# cpu.net
KiCad netlist of a schematic drawn in Altium Designer
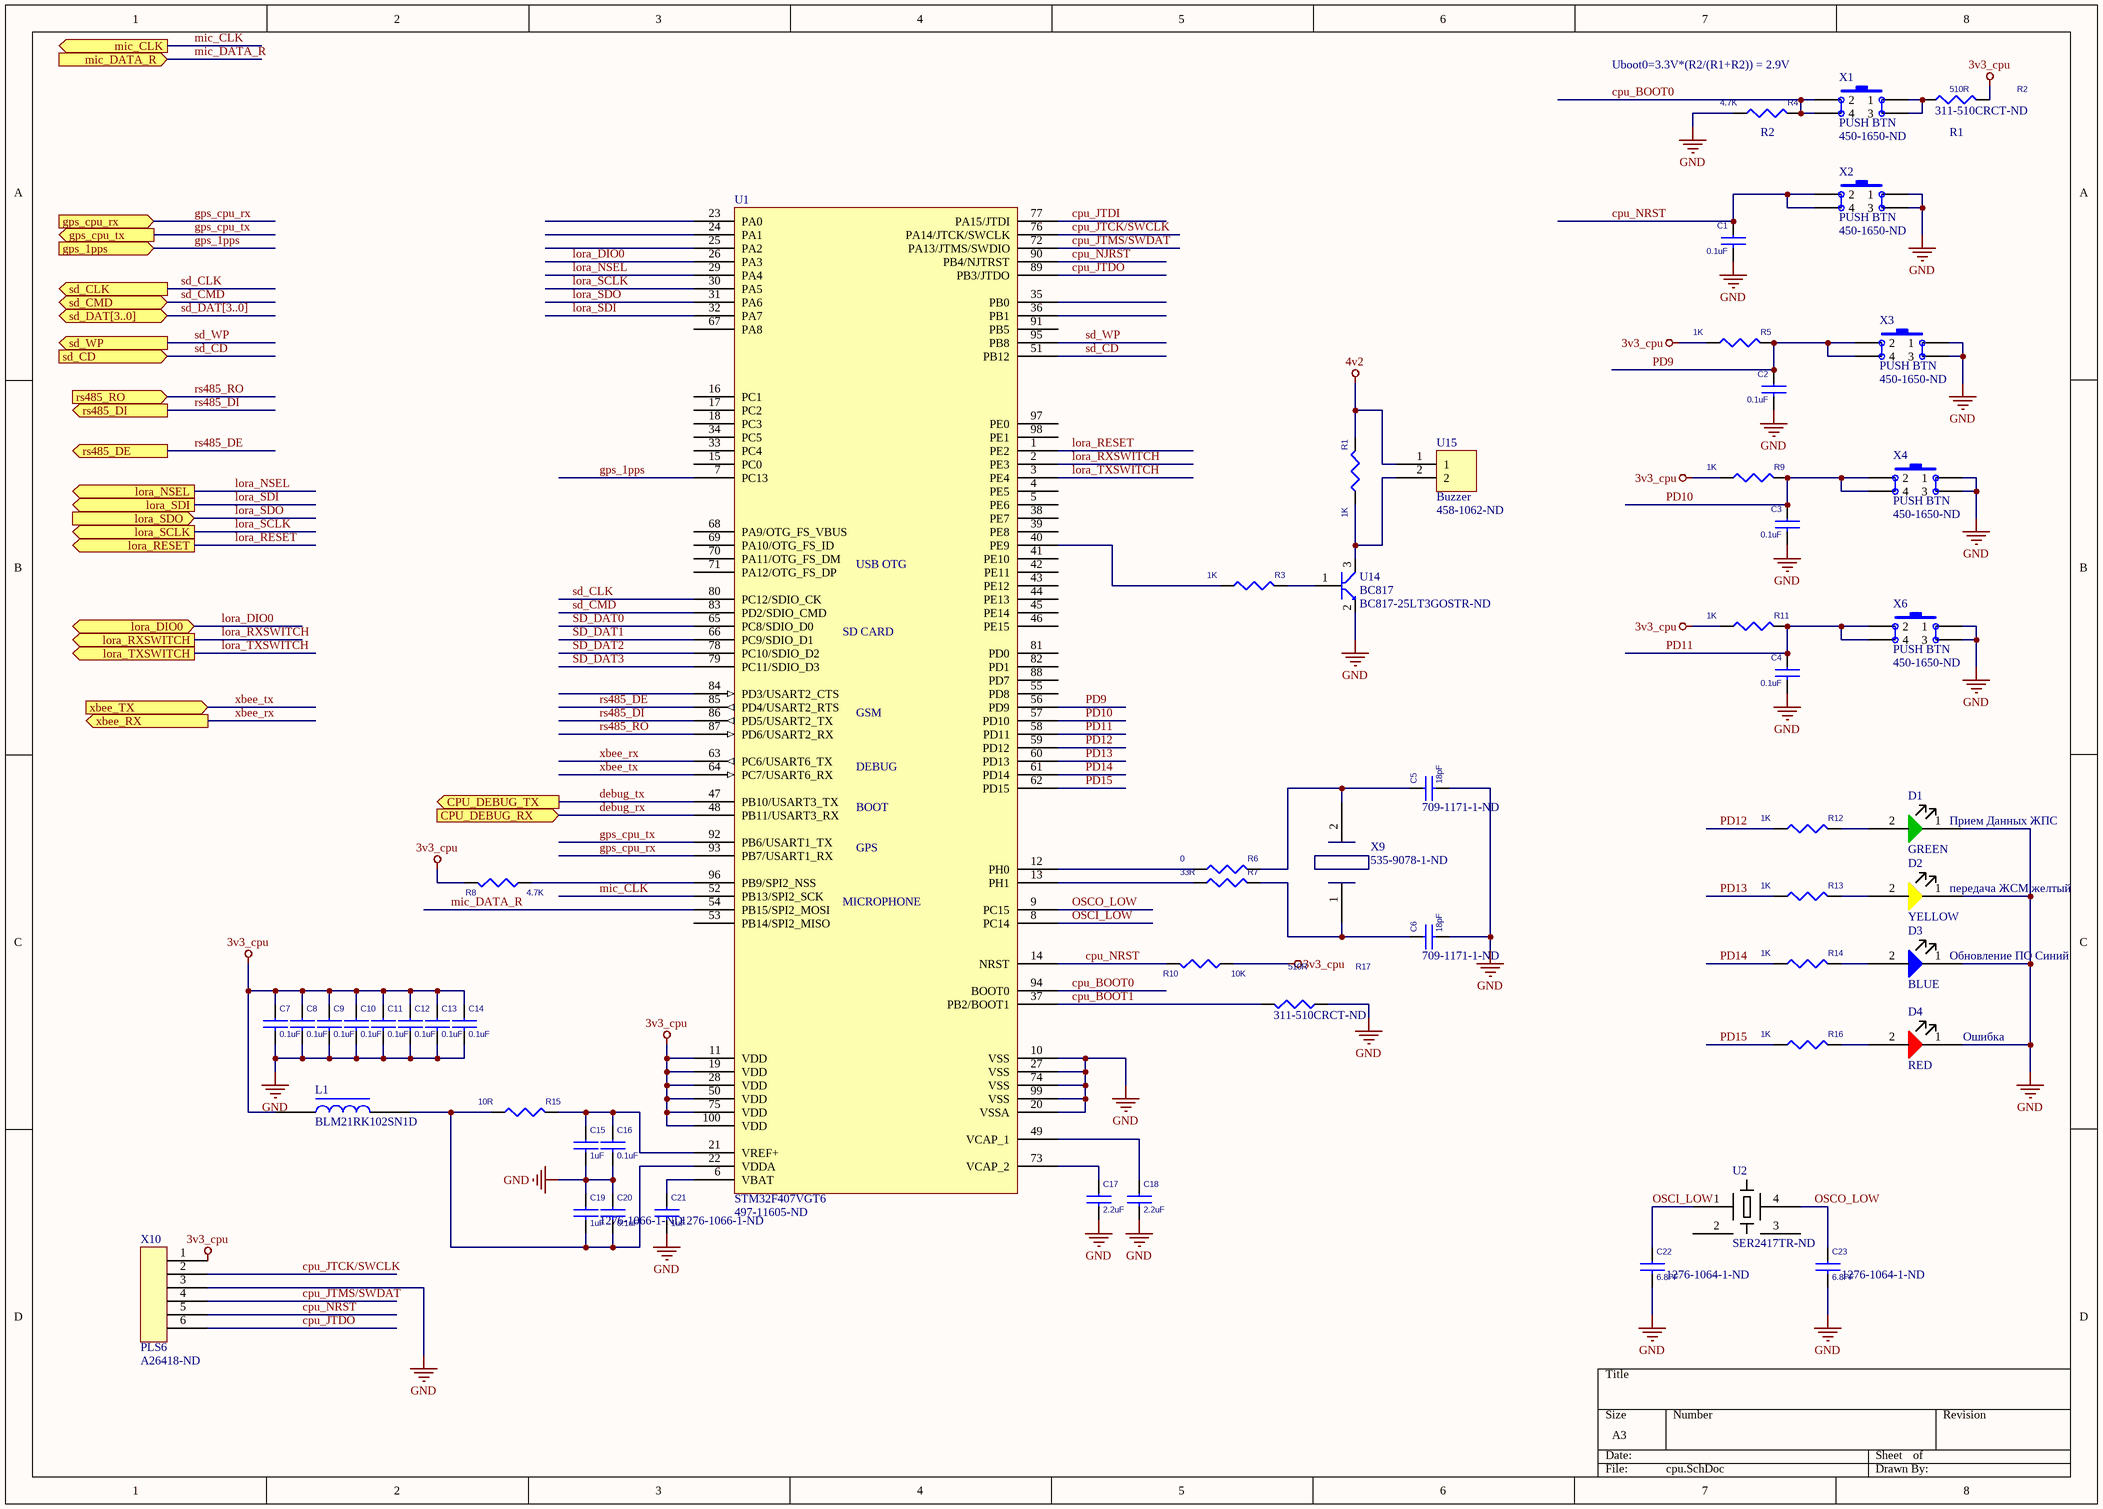
[diagram p0: cpu.SchDoc]

(export (version "E")
  (design (tool "Eeschema 10.0.6"))
  (components
    (comp (ref "C1")
      (value "0.1uF")
      (footprint "CAPC2012X09M")
      (description "CAP CER 0.1UF 25V 10% X7R 0805")
      (libsource (lib "Capacitors") (part "CAP_SMD_0.1UF_10%"))
    )
    (comp (ref "C2")
      (value "0.1uF")
      (footprint "CAPC2012X09M")
      (description "CAP CER 0.1UF 25V 10% X7R 0805")
      (libsource (lib "Capacitors") (part "CAP_SMD_0.1UF_10%"))
    )
    (comp (ref "C3")
      (value "0.1uF")
      (footprint "CAPC2012X09M")
      (description "CAP CER 0.1UF 25V 10% X7R 0805")
      (libsource (lib "Capacitors") (part "CAP_SMD_0.1UF_10%"))
    )
    (comp (ref "C4")
      (value "0.1uF")
      (footprint "CAPC2012X09M")
      (description "CAP CER 0.1UF 25V 10% X7R 0805")
      (libsource (lib "Capacitors") (part "CAP_SMD_0.1UF_10%"))
    )
    (comp (ref "C5")
      (value "18pF")
      (footprint "CAPC2012X09M")
      (description "CAP CER 27PF 200V 5% NP0 0805")
      (fields (field (name "SUPPLIER PART NUMBER 1") "709-1171-1-ND"))
      (libsource (lib "Capacitors") (part "CAP_SMD_18PF_5%"))
    )
    (comp (ref "C6")
      (value "18pF")
      (footprint "CAPC2012X09M")
      (description "CAP CER 27PF 200V 5% NP0 0805")
      (fields (field (name "SUPPLIER PART NUMBER 1") "709-1171-1-ND"))
      (libsource (lib "Capacitors") (part "CAP_SMD_18PF_5%"))
    )
    (comp (ref "C7")
      (value "0.1uF")
      (footprint "CAPC2012X09M")
      (description "CAP CER 0.1UF 25V 10% X7R 0805")
      (libsource (lib "Capacitors") (part "CAP_SMD_0.1UF_10%"))
    )
    (comp (ref "C8")
      (value "0.1uF")
      (footprint "CAPC2012X09M")
      (description "CAP CER 0.1UF 25V 10% X7R 0805")
      (libsource (lib "Capacitors") (part "CAP_SMD_0.1UF_10%"))
    )
    (comp (ref "C9")
      (value "0.1uF")
      (footprint "CAPC2012X09M")
      (description "CAP CER 0.1UF 25V 10% X7R 0805")
      (libsource (lib "Capacitors") (part "CAP_SMD_0.1UF_10%"))
    )
    (comp (ref "C10")
      (value "0.1uF")
      (footprint "CAPC2012X09M")
      (description "CAP CER 0.1UF 25V 10% X7R 0805")
      (libsource (lib "Capacitors") (part "CAP_SMD_0.1UF_10%"))
    )
    (comp (ref "C11")
      (value "0.1uF")
      (footprint "CAPC2012X09M")
      (description "CAP CER 0.1UF 25V 10% X7R 0805")
      (libsource (lib "Capacitors") (part "CAP_SMD_0.1UF_10%"))
    )
    (comp (ref "C12")
      (value "0.1uF")
      (footprint "CAPC2012X09M")
      (description "CAP CER 0.1UF 25V 10% X7R 0805")
      (libsource (lib "Capacitors") (part "CAP_SMD_0.1UF_10%"))
    )
    (comp (ref "C13")
      (value "0.1uF")
      (footprint "CAPC2012X09M")
      (description "CAP CER 0.1UF 25V 10% X7R 0805")
      (libsource (lib "Capacitors") (part "CAP_SMD_0.1UF_10%"))
    )
    (comp (ref "C14")
      (value "0.1uF")
      (footprint "CAPC2012X09M")
      (description "CAP CER 0.1UF 25V 10% X7R 0805")
      (libsource (lib "Capacitors") (part "CAP_SMD_0.1UF_10%"))
    )
    (comp (ref "C15")
      (value "1uF")
      (footprint "CAPC2012X09M")
      (description "MLCC; 1uF; 25V; X7R; ±10%; SMD; 0805;")
      (libsource (lib "Capacitors") (part "CAP_SMD_1uF_10%"))
    )
    (comp (ref "C16")
      (value "0.1uF")
      (footprint "CAPC2012X09M")
      (description "CAP CER 0.1UF 25V 10% X7R 0805")
      (libsource (lib "Capacitors") (part "CAP_SMD_0.1UF_10%"))
    )
    (comp (ref "C17")
      (value "2.2uF")
      (footprint "CAPC2012X09M")
      (description "CAP CER 2.2UF 16V 10% X5R 0805")
      (libsource (lib "Capacitors") (part "CAP_SMD_2.2uF_10%"))
    )
    (comp (ref "C18")
      (value "2.2uF")
      (footprint "CAPC2012X09M")
      (description "CAP CER 2.2UF 16V 10% X5R 0805")
      (libsource (lib "Capacitors") (part "CAP_SMD_2.2uF_10%"))
    )
    (comp (ref "C19")
      (value "1uF")
      (footprint "CAPC2012X09M")
      (description "MLCC; 1uF; 25V; X7R; ±10%; SMD; 0805;")
      (fields (field (name "SUPPLIER PART NUMBER 1") "1276-1066-1-ND"))
      (libsource (lib "Capacitors") (part "CAP_SMD_1uF_10%"))
    )
    (comp (ref "C20")
      (value "0.1uF")
      (footprint "CAPC2012X09M")
      (description "CAP CER 0.1UF 25V 10% X7R 0805")
      (libsource (lib "Capacitors") (part "CAP_SMD_0.1UF_10%"))
    )
    (comp (ref "C21")
      (value "1uF")
      (footprint "CAPC2012X09M")
      (description "MLCC; 1uF; 25V; X7R; ±10%; SMD; 0805;")
      (fields (field (name "SUPPLIER PART NUMBER 1") "1276-1066-1-ND"))
      (libsource (lib "Capacitors") (part "CAP_SMD_1uF_10%"))
    )
    (comp (ref "C22")
      (value "6.8PF")
      (footprint "CAPC2012X09M")
      (description "CAP MLCC 6.8PF 50V 5% NP0 0805")
      (fields (field (name "SUPPLIER PART NUMBER 1") "1276-1064-1-ND"))
      (libsource (lib "Capacitors") (part "CAP_SMD_6.8PF_5%"))
    )
    (comp (ref "C23")
      (value "6.8PF")
      (footprint "CAPC2012X09M")
      (description "CAP MLCC 6.8PF 50V 5% NP0 0805")
      (fields (field (name "SUPPLIER PART NUMBER 1") "1276-1064-1-ND"))
      (libsource (lib "Capacitors") (part "CAP_SMD_6.8PF_5%"))
    )
    (comp (ref "D1")
      (value "GREEN")
      (footprint "DIOC2012X11N")
      (libsource (lib "Passive") (part "LED_GREEN"))
    )
    (comp (ref "D2")
      (value "YELLOW")
      (footprint "DIOC2012X11N")
      (libsource (lib "Passive") (part "LED_YELLOW"))
    )
    (comp (ref "D3") (value "BLUE") (footprint "DIOC2012X11N") (libsource (lib "Passive") (part "LED_BLUE")))
    (comp (ref "D4") (value "RED") (footprint "DIOC2012X11N") (libsource (lib "Passive") (part "LED_RED")))
    (comp (ref "L1")
      (value "BLM21RK102SN1D")
      (footprint "DIOC2012X11N")
      (libsource (lib "Passive") (part "BLM21RK102SN1D"))
    )
    (comp (ref "R1")
      (value "1K")
      (footprint "RESC2013X06M")
      (description "RES - 1K OHM, 5%, 1/8W, 0805 SMD")
      (libsource (lib "Resistors") (part "RES_SMD_1K_5%"))
    )
    (comp (ref "R2")
      (value "510R")
      (footprint "RESC2013X06M")
      (description "RES - 510 OHM, 5%, 1/8W, 0805 SMD")
      (fields (field (name "SUPPLIER PART NUMBER 1") "311-510CRCT-ND"))
      (libsource (lib "Resistors") (part "RES_SMD_510_5%"))
    )
    (comp (ref "R3")
      (value "1K")
      (footprint "RESC2013X06M")
      (description "RES - 1K OHM, 5%, 1/8W, 0805 SMD")
      (libsource (lib "Resistors") (part "RES_SMD_1K_5%"))
    )
    (comp (ref "R4")
      (value "4.7K")
      (footprint "RESC2013X06M")
      (description "RES 4.7K OHM 1/8W 1% 0805 SMD")
      (libsource (lib "Resistors") (part "RES_SMD_4.7K_1%"))
    )
    (comp (ref "R5")
      (value "1K")
      (footprint "RESC2013X06M")
      (description "RES - 1K OHM, 5%, 1/8W, 0805 SMD")
      (libsource (lib "Resistors") (part "RES_SMD_1K_5%"))
    )
    (comp (ref "R6")
      (value "0")
      (footprint "RESC2013X06M")
      (description "RES 0.0 OHM 1/8W JUMP 0805 SMD")
      (libsource (lib "Resistors") (part "RES_SMD_0"))
    )
    (comp (ref "R7")
      (value "33R")
      (footprint "RESC2013X06M")
      (description "RES - 33 OHM, 5%, 1/8W, 0805 SMD")
      (libsource (lib "Resistors") (part "RES_SMD_33R_5%"))
    )
    (comp (ref "R8")
      (value "4.7K")
      (footprint "RESC2013X06M")
      (description "RES 4.7K OHM 1/8W 1% 0805 SMD")
      (libsource (lib "Resistors") (part "RES_SMD_4.7K_1%"))
    )
    (comp (ref "R9")
      (value "1K")
      (footprint "RESC2013X06M")
      (description "RES - 1K OHM, 5%, 1/8W, 0805 SMD")
      (libsource (lib "Resistors") (part "RES_SMD_1K_5%"))
    )
    (comp (ref "R10")
      (value "10K")
      (footprint "RESC2013X06M")
      (description "RES 10K OHM 1/8W 5% 0805 SMD")
      (libsource (lib "Resistors") (part "RES_SMD_10K_5%"))
    )
    (comp (ref "R11")
      (value "1K")
      (footprint "RESC2013X06M")
      (description "RES - 1K OHM, 5%, 1/8W, 0805 SMD")
      (libsource (lib "Resistors") (part "RES_SMD_1K_5%"))
    )
    (comp (ref "R12")
      (value "1K")
      (footprint "RESC2013X06M")
      (description "RES - 1K OHM, 5%, 1/8W, 0805 SMD")
      (libsource (lib "Resistors") (part "RES_SMD_1K_5%"))
    )
    (comp (ref "R13")
      (value "1K")
      (footprint "RESC2013X06M")
      (description "RES - 1K OHM, 5%, 1/8W, 0805 SMD")
      (libsource (lib "Resistors") (part "RES_SMD_1K_5%"))
    )
    (comp (ref "R14")
      (value "1K")
      (footprint "RESC2013X06M")
      (description "RES - 1K OHM, 5%, 1/8W, 0805 SMD")
      (libsource (lib "Resistors") (part "RES_SMD_1K_5%"))
    )
    (comp (ref "R15")
      (value "10R")
      (footprint "RESC2013X06M")
      (description "RES 10 OHM 1/8W 1% 0805 SMD")
      (libsource (lib "Resistors") (part "RES_SMD_10R_5%"))
    )
    (comp (ref "R16")
      (value "1K")
      (footprint "RESC2013X06M")
      (description "RES - 1K OHM, 5%, 1/8W, 0805 SMD")
      (libsource (lib "Resistors") (part "RES_SMD_1K_5%"))
    )
    (comp (ref "R17")
      (value "510R")
      (footprint "RESC2013X06M")
      (description "RES - 510 OHM, 5%, 1/8W, 0805 SMD")
      (fields (field (name "SUPPLIER PART NUMBER 1") "311-510CRCT-ND"))
      (libsource (lib "Resistors") (part "RES_SMD_510_5%"))
    )
    (comp (ref "U1")
      (value "STM32F407VGT6")
      (footprint "TSQFP50P1600X1600X160-100M")
      (fields (field (name "SUPPLIER PART NUMBER 1") "497-11605-ND"))
      (libsource (lib "TruthEar") (part "STM32F407VGT6"))
    )
    (comp (ref "U2")
      (value "32.768KHZ")
      (footprint "SOJ550P380X254-4M")
      (fields (field (name "SUPPLIER PART NUMBER 1") "SER2417TR-ND"))
      (libsource (lib "TruthEar") (part "MC-306"))
    )
    (comp (ref "U14")
      (value "BC817")
      (footprint "SOT95P237X111-3N_SOT-23")
      (fields (field (name "SUPPLIER PART NUMBER 1") "BC817-25LT3GOSTR-ND"))
      (libsource (lib "TruthEar") (part "BC817"))
    )
    (comp (ref "U15")
      (value "Buzzer")
      (footprint "pb1224pe")
      (fields (field (name "SUPPLIER PART NUMBER 1") "458-1062-ND"))
      (libsource (lib "TruthEar") (part "pb-1224pe-05q"))
    )
    (comp (ref "X1")
      (value "PUSH BTN")
      (footprint "PUSHBTN")
      (fields (field (name "SUPPLIER PART NUMBER 1") "450-1650-ND"))
      (libsource (lib "TruthEar") (part "SW1"))
    )
    (comp (ref "X2")
      (value "PUSH BTN")
      (footprint "PUSHBTN")
      (fields (field (name "SUPPLIER PART NUMBER 1") "450-1650-ND"))
      (libsource (lib "TruthEar") (part "SW1"))
    )
    (comp (ref "X3")
      (value "PUSH BTN")
      (footprint "PUSHBTN")
      (fields (field (name "SUPPLIER PART NUMBER 1") "450-1650-ND"))
      (libsource (lib "TruthEar") (part "SW1"))
    )
    (comp (ref "X4")
      (value "PUSH BTN")
      (footprint "PUSHBTN")
      (fields (field (name "SUPPLIER PART NUMBER 1") "450-1650-ND"))
      (libsource (lib "TruthEar") (part "SW1"))
    )
    (comp (ref "X6")
      (value "PUSH BTN")
      (footprint "PUSHBTN")
      (fields (field (name "SUPPLIER PART NUMBER 1") "450-1650-ND"))
      (libsource (lib "TruthEar") (part "SW1"))
    )
    (comp (ref "X9")
      (value "25.000Mhz")
      (footprint "SODFL1270X420-2L")
      (fields (field (name "SUPPLIER PART NUMBER 1") "535-9078-1-ND"))
      (libsource (lib "TruthEar") (part "OSC25M"))
    )
    (comp (ref "X10")
      (value "PLS6")
      (footprint "PLS6")
      (fields (field (name "SUPPLIER PART NUMBER 1") "A26418-ND"))
      (libsource (lib "Connectors") (part "PLS6"))
    )
  )
  (nets
    (net (code "5") (name "/OSCI_LOW") (class "Default")
      (node (ref "C22") (pin "1") (pinfunction "1_1") (pintype "passive"))
      (node (ref "U1") (pin "8") (pinfunction "PC14_8") (pintype "passive"))
      (node (ref "U2") (pin "1") (pinfunction "OSC1_1") (pintype "power_in"))
    )
    (net (code "6") (name "/OSCO_LOW") (class "Default")
      (node (ref "C23") (pin "1") (pinfunction "1_1") (pintype "passive"))
      (node (ref "U1") (pin "9") (pinfunction "PC15_9") (pintype "passive"))
      (node (ref "U2") (pin "4") (pinfunction "OSC2_4") (pintype "power_in"))
    )
    (net (code "7") (name "/PD9") (class "Default")
      (node (ref "C2") (pin "1") (pinfunction "1_1") (pintype "passive"))
      (node (ref "R5") (pin "2") (pinfunction "2_2") (pintype "passive"))
      (node (ref "U1") (pin "56") (pinfunction "PD9_56") (pintype "passive"))
      (node (ref "X3") (pin "2") (pinfunction "2_2") (pintype "passive"))
      (node (ref "X3") (pin "4") (pinfunction "4_4") (pintype "passive"))
    )
    (net (code "8") (name "/PD10") (class "Default")
      (node (ref "C3") (pin "1") (pinfunction "1_1") (pintype "passive"))
      (node (ref "R9") (pin "2") (pinfunction "2_2") (pintype "passive"))
      (node (ref "U1") (pin "57") (pinfunction "PD10_57") (pintype "passive"))
      (node (ref "X4") (pin "2") (pinfunction "2_2") (pintype "passive"))
      (node (ref "X4") (pin "4") (pinfunction "4_4") (pintype "passive"))
    )
    (net (code "9") (name "/PD11") (class "Default")
      (node (ref "C4") (pin "1") (pinfunction "1_1") (pintype "passive"))
      (node (ref "R11") (pin "2") (pinfunction "2_2") (pintype "passive"))
      (node (ref "U1") (pin "58") (pinfunction "PD11_58") (pintype "passive"))
      (node (ref "X6") (pin "2") (pinfunction "2_2") (pintype "passive"))
      (node (ref "X6") (pin "4") (pinfunction "4_4") (pintype "passive"))
    )
    (net (code "10") (name "/PD12") (class "Default")
      (node (ref "R12") (pin "1") (pinfunction "1_1") (pintype "passive"))
      (node (ref "U1") (pin "59") (pinfunction "PD12_59") (pintype "passive"))
    )
    (net (code "11") (name "/PD13") (class "Default")
      (node (ref "R13") (pin "1") (pinfunction "1_1") (pintype "passive"))
      (node (ref "U1") (pin "60") (pinfunction "PD13_60") (pintype "passive"))
    )
    (net (code "12") (name "/PD14") (class "Default")
      (node (ref "R14") (pin "1") (pinfunction "1_1") (pintype "passive"))
      (node (ref "U1") (pin "61") (pinfunction "PD14_61") (pintype "passive"))
    )
    (net (code "13") (name "/PD15") (class "Default")
      (node (ref "R16") (pin "1") (pinfunction "1_1") (pintype "passive"))
      (node (ref "U1") (pin "62") (pinfunction "PD15_62") (pintype "passive"))
    )
    (net (code "14") (name "/SD_DAT0") (class "Default")
      (node (ref "U1") (pin "65") (pinfunction "PC8/SDIO_D0_65") (pintype "passive"))
    )
    (net (code "15") (name "/SD_DAT1") (class "Default")
      (node (ref "U1") (pin "66") (pinfunction "PC9/SDIO_D1_66") (pintype "passive"))
    )
    (net (code "16") (name "/SD_DAT2") (class "Default")
      (node (ref "U1") (pin "78") (pinfunction "PC10/SDIO_D2_78") (pintype "passive"))
    )
    (net (code "17") (name "/SD_DAT3") (class "Default")
      (node (ref "U1") (pin "79") (pinfunction "PC11/SDIO_D3_79") (pintype "passive"))
    )
    (net (code "18") (name "/cpu_BOOT0") (class "Default")
      (node (ref "R4") (pin "2") (pinfunction "2_2") (pintype "passive"))
      (node (ref "U1") (pin "94") (pinfunction "BOOT0_94") (pintype "passive"))
      (node (ref "X1") (pin "2") (pinfunction "2_2") (pintype "passive"))
      (node (ref "X1") (pin "4") (pinfunction "4_4") (pintype "passive"))
    )
    (net (code "19") (name "/cpu_BOOT1") (class "Default")
      (node (ref "R17") (pin "2") (pinfunction "2_2") (pintype "passive"))
      (node (ref "U1") (pin "37") (pinfunction "PB2/BOOT1_37") (pintype "passive"))
    )
    (net (code "20") (name "/cpu_JTCK{slash}SWCLK") (class "Default")
      (node (ref "U1") (pin "76") (pinfunction "PA14/JTCK/SWCLK_76") (pintype "passive"))
      (node (ref "X10") (pin "2") (pinfunction "2_2") (pintype "power_in"))
    )
    (net (code "21") (name "/cpu_JTDI") (class "Default")
      (node (ref "U1") (pin "77") (pinfunction "PA15/JTDI_77") (pintype "passive"))
    )
    (net (code "22") (name "/cpu_JTDO") (class "Default")
      (node (ref "U1") (pin "89") (pinfunction "PB3/JTDO_89") (pintype "passive"))
      (node (ref "X10") (pin "6") (pinfunction "6_6") (pintype "power_in"))
    )
    (net (code "23") (name "/cpu_JTMS{slash}SWDAT") (class "Default")
      (node (ref "U1") (pin "72") (pinfunction "PA13/JTMS/SWDIO_72") (pintype "passive"))
      (node (ref "X10") (pin "4") (pinfunction "4_4") (pintype "power_in"))
    )
    (net (code "24") (name "/cpu_NJRST") (class "Default")
      (node (ref "U1") (pin "90") (pinfunction "PB4/NJTRST_90") (pintype "passive"))
    )
    (net (code "25") (name "/cpu_NRST") (class "Default")
      (node (ref "C1") (pin "1") (pinfunction "1_1") (pintype "passive"))
      (node (ref "R10") (pin "2") (pinfunction "2_2") (pintype "passive"))
      (node (ref "U1") (pin "14") (pinfunction "NRST_14") (pintype "passive"))
      (node (ref "X10") (pin "5") (pinfunction "5_5") (pintype "power_in"))
      (node (ref "X2") (pin "2") (pinfunction "2_2") (pintype "passive"))
      (node (ref "X2") (pin "4") (pinfunction "4_4") (pintype "passive"))
    )
    (net (code "26") (name "/debug_rx") (class "Default")
      (node (ref "U1") (pin "48") (pinfunction "PB11/USART3_RX_48") (pintype "passive"))
    )
    (net (code "27") (name "/debug_tx") (class "Default")
      (node (ref "U1") (pin "47") (pinfunction "PB10/USART3_TX_47") (pintype "passive"))
    )
    (net (code "28") (name "/gps_1pps") (class "Default")
      (node (ref "U1") (pin "7") (pinfunction "PC13_7") (pintype "passive"))
    )
    (net (code "29") (name "/gps_cpu_rx") (class "Default")
      (node (ref "U1") (pin "93") (pinfunction "PB7/USART1_RX_93") (pintype "passive"))
    )
    (net (code "30") (name "/gps_cpu_tx") (class "Default")
      (node (ref "U1") (pin "92") (pinfunction "PB6/USART1_TX_92") (pintype "passive"))
    )
    (net (code "31") (name "/lora_DIO0") (class "Default")
      (node (ref "U1") (pin "26") (pinfunction "PA3_26") (pintype "passive"))
    )
    (net (code "32") (name "/lora_NSEL") (class "Default")
      (node (ref "U1") (pin "29") (pinfunction "PA4_29") (pintype "passive"))
    )
    (net (code "33") (name "/lora_RESET") (class "Default")
      (node (ref "U1") (pin "1") (pinfunction "PE2_1") (pintype "passive"))
    )
    (net (code "34") (name "/lora_RXSWITCH") (class "Default")
      (node (ref "U1") (pin "2") (pinfunction "PE3_2") (pintype "passive"))
    )
    (net (code "35") (name "/lora_SCLK") (class "Default")
      (node (ref "U1") (pin "30") (pinfunction "PA5_30") (pintype "passive"))
    )
    (net (code "36") (name "/lora_SDI") (class "Default")
      (node (ref "U1") (pin "32") (pinfunction "PA7_32") (pintype "passive"))
    )
    (net (code "37") (name "/lora_SDO") (class "Default")
      (node (ref "U1") (pin "31") (pinfunction "PA6_31") (pintype "passive"))
    )
    (net (code "38") (name "/lora_TXSWITCH") (class "Default")
      (node (ref "U1") (pin "3") (pinfunction "PE4_3") (pintype "passive"))
    )
    (net (code "39") (name "/mic_CLK") (class "Default")
      (node (ref "U1") (pin "52") (pinfunction "PB13/SPI2_SCK_52") (pintype "passive"))
    )
    (net (code "40") (name "/mic_DATA_R") (class "Default")
      (node (ref "U1") (pin "54") (pinfunction "PB15/SPI2_MOSI_54") (pintype "passive"))
    )
    (net (code "41") (name "/rs485_DE") (class "Default")
      (node (ref "U1") (pin "85") (pinfunction "PD4/USART2_RTS_85") (pintype "output"))
    )
    (net (code "42") (name "/rs485_DI") (class "Default")
      (node (ref "U1") (pin "86") (pinfunction "PD5/USART2_TX_86") (pintype "output"))
    )
    (net (code "43") (name "/rs485_RO") (class "Default")
      (node (ref "U1") (pin "87") (pinfunction "PD6/USART2_RX_87") (pintype "input"))
    )
    (net (code "44") (name "/sd_CD") (class "Default")
      (node (ref "U1") (pin "51") (pinfunction "PB12_51") (pintype "passive"))
    )
    (net (code "45") (name "/sd_CLK") (class "Default")
      (node (ref "U1") (pin "80") (pinfunction "PC12/SDIO_CK_80") (pintype "passive"))
    )
    (net (code "46") (name "/sd_CMD") (class "Default")
      (node (ref "U1") (pin "83") (pinfunction "PD2/SDIO_CMD_83") (pintype "passive"))
    )
    (net (code "48") (name "/sd_WP") (class "Default")
      (node (ref "U1") (pin "95") (pinfunction "PB8_95") (pintype "passive"))
    )
    (net (code "49") (name "/xbee_rx") (class "Default")
      (node (ref "U1") (pin "63") (pinfunction "PC6/USART6_TX_63") (pintype "output"))
    )
    (net (code "50") (name "/xbee_tx") (class "Default")
      (node (ref "U1") (pin "64") (pinfunction "PC7/USART6_RX_64") (pintype "input"))
    )
    (net (code "51") (name "3v3_cpu") (class "Default")
      (node (ref "C10") (pin "1") (pinfunction "1_1") (pintype "passive"))
      (node (ref "C11") (pin "1") (pinfunction "1_1") (pintype "passive"))
      (node (ref "C12") (pin "1") (pinfunction "1_1") (pintype "passive"))
      (node (ref "C13") (pin "1") (pinfunction "1_1") (pintype "passive"))
      (node (ref "C14") (pin "1") (pinfunction "1_1") (pintype "passive"))
      (node (ref "C7") (pin "1") (pinfunction "1_1") (pintype "passive"))
      (node (ref "C8") (pin "1") (pinfunction "1_1") (pintype "passive"))
      (node (ref "C9") (pin "1") (pinfunction "1_1") (pintype "passive"))
      (node (ref "L1") (pin "1") (pinfunction "1_1") (pintype "passive"))
      (node (ref "R10") (pin "1") (pinfunction "1_1") (pintype "passive"))
      (node (ref "R11") (pin "1") (pinfunction "1_1") (pintype "passive"))
      (node (ref "R2") (pin "1") (pinfunction "1_1") (pintype "passive"))
      (node (ref "R5") (pin "1") (pinfunction "1_1") (pintype "passive"))
      (node (ref "R8") (pin "2") (pinfunction "2_2") (pintype "passive"))
      (node (ref "R9") (pin "1") (pinfunction "1_1") (pintype "passive"))
      (node (ref "U1") (pin "100") (pinfunction "VDD_100") (pintype "passive"))
      (node (ref "U1") (pin "11") (pinfunction "VDD_11") (pintype "passive"))
      (node (ref "U1") (pin "19") (pinfunction "VDD_19") (pintype "passive"))
      (node (ref "U1") (pin "28") (pinfunction "VDD_28") (pintype "passive"))
      (node (ref "U1") (pin "50") (pinfunction "VDD_50") (pintype "passive"))
      (node (ref "U1") (pin "75") (pinfunction "VDD_75") (pintype "passive"))
      (node (ref "X10") (pin "1") (pinfunction "1_1") (pintype "power_in"))
    )
    (net (code "52") (name "4v2") (class "Default")
      (node (ref "R1") (pin "2") (pinfunction "2_2") (pintype "passive"))
      (node (ref "U15") (pin "1") (pinfunction "1_1") (pintype "passive"))
    )
    (net (code "53") (name "GND") (class "Default")
      (node (ref "C1") (pin "2") (pinfunction "2_2") (pintype "passive"))
      (node (ref "C10") (pin "2") (pinfunction "2_2") (pintype "passive"))
      (node (ref "C11") (pin "2") (pinfunction "2_2") (pintype "passive"))
      (node (ref "C12") (pin "2") (pinfunction "2_2") (pintype "passive"))
      (node (ref "C13") (pin "2") (pinfunction "2_2") (pintype "passive"))
      (node (ref "C14") (pin "2") (pinfunction "2_2") (pintype "passive"))
      (node (ref "C15") (pin "2") (pinfunction "2_2") (pintype "passive"))
      (node (ref "C16") (pin "2") (pinfunction "2_2") (pintype "passive"))
      (node (ref "C17") (pin "2") (pinfunction "2_2") (pintype "passive"))
      (node (ref "C18") (pin "2") (pinfunction "2_2") (pintype "passive"))
      (node (ref "C19") (pin "1") (pinfunction "1_1") (pintype "passive"))
      (node (ref "C2") (pin "2") (pinfunction "2_2") (pintype "passive"))
      (node (ref "C20") (pin "1") (pinfunction "1_1") (pintype "passive"))
      (node (ref "C21") (pin "2") (pinfunction "2_2") (pintype "passive"))
      (node (ref "C22") (pin "2") (pinfunction "2_2") (pintype "passive"))
      (node (ref "C23") (pin "2") (pinfunction "2_2") (pintype "passive"))
      (node (ref "C3") (pin "2") (pinfunction "2_2") (pintype "passive"))
      (node (ref "C4") (pin "2") (pinfunction "2_2") (pintype "passive"))
      (node (ref "C5") (pin "2") (pinfunction "2_2") (pintype "passive"))
      (node (ref "C6") (pin "2") (pinfunction "2_2") (pintype "passive"))
      (node (ref "C7") (pin "2") (pinfunction "2_2") (pintype "passive"))
      (node (ref "C8") (pin "2") (pinfunction "2_2") (pintype "passive"))
      (node (ref "C9") (pin "2") (pinfunction "2_2") (pintype "passive"))
      (node (ref "D1") (pin "1") (pinfunction "C_1") (pintype "passive"))
      (node (ref "D2") (pin "1") (pinfunction "C_1") (pintype "passive"))
      (node (ref "D3") (pin "1") (pinfunction "C_1") (pintype "passive"))
      (node (ref "D4") (pin "1") (pinfunction "C_1") (pintype "passive"))
      (node (ref "R17") (pin "1") (pinfunction "1_1") (pintype "passive"))
      (node (ref "R4") (pin "1") (pinfunction "1_1") (pintype "passive"))
      (node (ref "U1") (pin "10") (pinfunction "VSS_10") (pintype "passive"))
      (node (ref "U1") (pin "20") (pinfunction "VSSA_20") (pintype "passive"))
      (node (ref "U1") (pin "27") (pinfunction "VSS_27") (pintype "passive"))
      (node (ref "U1") (pin "74") (pinfunction "VSS_74") (pintype "passive"))
      (node (ref "U1") (pin "99") (pinfunction "VSS_99") (pintype "passive"))
      (node (ref "U14") (pin "2") (pinfunction "E_2") (pintype "passive"))
      (node (ref "X10") (pin "3") (pinfunction "3_3") (pintype "power_in"))
      (node (ref "X2") (pin "1") (pinfunction "1_1") (pintype "passive"))
      (node (ref "X2") (pin "3") (pinfunction "3_3") (pintype "passive"))
      (node (ref "X3") (pin "1") (pinfunction "1_1") (pintype "passive"))
      (node (ref "X3") (pin "3") (pinfunction "3_3") (pintype "passive"))
      (node (ref "X4") (pin "1") (pinfunction "1_1") (pintype "passive"))
      (node (ref "X4") (pin "3") (pinfunction "3_3") (pintype "passive"))
      (node (ref "X6") (pin "1") (pinfunction "1_1") (pintype "passive"))
      (node (ref "X6") (pin "3") (pinfunction "3_3") (pintype "passive"))
    )
    (net (code "54") (name "Net-(C5-Pad1)") (class "Default")
      (node (ref "C5") (pin "1") (pinfunction "1_1") (pintype "passive"))
      (node (ref "R6") (pin "2") (pinfunction "2_2") (pintype "passive"))
      (node (ref "X9") (pin "2") (pinfunction "2_2") (pintype "power_in"))
    )
    (net (code "55") (name "Net-(C6-Pad1)") (class "Default")
      (node (ref "C6") (pin "1") (pinfunction "1_1") (pintype "passive"))
      (node (ref "R7") (pin "2") (pinfunction "2_2") (pintype "passive"))
      (node (ref "X9") (pin "1") (pinfunction "1_1") (pintype "power_in"))
    )
    (net (code "56") (name "Net-(D1-A)") (class "Default")
      (node (ref "D1") (pin "2") (pinfunction "A_2") (pintype "passive"))
      (node (ref "R12") (pin "2") (pinfunction "2_2") (pintype "passive"))
    )
    (net (code "57") (name "Net-(D2-A)") (class "Default")
      (node (ref "D2") (pin "2") (pinfunction "A_2") (pintype "passive"))
      (node (ref "R13") (pin "2") (pinfunction "2_2") (pintype "passive"))
    )
    (net (code "58") (name "Net-(D3-A)") (class "Default")
      (node (ref "D3") (pin "2") (pinfunction "A_2") (pintype "passive"))
      (node (ref "R14") (pin "2") (pinfunction "2_2") (pintype "passive"))
    )
    (net (code "59") (name "Net-(D4-A)") (class "Default")
      (node (ref "D4") (pin "2") (pinfunction "A_2") (pintype "passive"))
      (node (ref "R16") (pin "2") (pinfunction "2_2") (pintype "passive"))
    )
    (net (code "60") (name "Net-(R2-Pad2)") (class "Default")
      (node (ref "R2") (pin "2") (pinfunction "2_2") (pintype "passive"))
      (node (ref "X1") (pin "1") (pinfunction "1_1") (pintype "passive"))
      (node (ref "X1") (pin "3") (pinfunction "3_3") (pintype "passive"))
    )
    (net (code "61") (name "Net-(U1-PB9{slash}SPI2_NSS)") (class "Default")
      (node (ref "R8") (pin "1") (pinfunction "1_1") (pintype "passive"))
      (node (ref "U1") (pin "96") (pinfunction "PB9/SPI2_NSS_96") (pintype "passive"))
    )
    (net (code "62") (name "Net-(U1-PE9)") (class "Default")
      (node (ref "R3") (pin "1") (pinfunction "1_1") (pintype "passive"))
      (node (ref "U1") (pin "40") (pinfunction "PE9_40") (pintype "passive"))
    )
    (net (code "63") (name "Net-(U1-PH0)") (class "Default")
      (node (ref "R6") (pin "1") (pinfunction "1_1") (pintype "passive"))
      (node (ref "U1") (pin "12") (pinfunction "PH0_12") (pintype "passive"))
    )
    (net (code "64") (name "Net-(U1-PH1)") (class "Default")
      (node (ref "R7") (pin "1") (pinfunction "1_1") (pintype "passive"))
      (node (ref "U1") (pin "13") (pinfunction "PH1_13") (pintype "passive"))
    )
    (net (code "65") (name "Net-(U1-VBAT)") (class "Default")
      (node (ref "C21") (pin "1") (pinfunction "1_1") (pintype "passive"))
      (node (ref "U1") (pin "6") (pinfunction "VBAT_6") (pintype "passive"))
    )
    (net (code "66") (name "Net-(U1-VCAP_1)") (class "Default")
      (node (ref "C18") (pin "1") (pinfunction "1_1") (pintype "passive"))
      (node (ref "U1") (pin "49") (pinfunction "VCAP_1_49") (pintype "passive"))
    )
    (net (code "67") (name "Net-(U1-VCAP_2)") (class "Default")
      (node (ref "C17") (pin "1") (pinfunction "1_1") (pintype "passive"))
      (node (ref "U1") (pin "73") (pinfunction "VCAP_2_73") (pintype "passive"))
    )
    (net (code "68") (name "Net-(U1-VDDA)") (class "Default")
      (node (ref "C19") (pin "2") (pinfunction "2_2") (pintype "passive"))
      (node (ref "C20") (pin "2") (pinfunction "2_2") (pintype "passive"))
      (node (ref "L1") (pin "2") (pinfunction "2_2") (pintype "passive"))
      (node (ref "R15") (pin "1") (pinfunction "1_1") (pintype "passive"))
      (node (ref "U1") (pin "22") (pinfunction "VDDA_22") (pintype "passive"))
    )
    (net (code "69") (name "Net-(U1-VREF+)") (class "Default")
      (node (ref "C15") (pin "1") (pinfunction "1_1") (pintype "passive"))
      (node (ref "C16") (pin "1") (pinfunction "1_1") (pintype "passive"))
      (node (ref "R15") (pin "2") (pinfunction "2_2") (pintype "passive"))
      (node (ref "U1") (pin "21") (pinfunction "VREF+_21") (pintype "passive"))
    )
    (net (code "70") (name "Net-(U14-B)") (class "Default")
      (node (ref "R3") (pin "2") (pinfunction "2_2") (pintype "passive"))
      (node (ref "U14") (pin "1") (pinfunction "B_1") (pintype "passive"))
    )
    (net (code "71") (name "Net-(U14-C)") (class "Default")
      (node (ref "R1") (pin "1") (pinfunction "1_1") (pintype "passive"))
      (node (ref "U14") (pin "3") (pinfunction "C_3") (pintype "passive"))
      (node (ref "U15") (pin "2") (pinfunction "2_2") (pintype "passive"))
    )
    (net (code "72") (name "unconnected-(U1-PA0-Pad23)") (class "Default")
      (node (ref "U1") (pin "23") (pinfunction "PA0_23") (pintype "passive"))
    )
    (net (code "73") (name "unconnected-(U1-PA1-Pad24)") (class "Default")
      (node (ref "U1") (pin "24") (pinfunction "PA1_24") (pintype "passive"))
    )
    (net (code "74") (name "unconnected-(U1-PA2-Pad25)") (class "Default")
      (node (ref "U1") (pin "25") (pinfunction "PA2_25") (pintype "passive"))
    )
    (net (code "75") (name "unconnected-(U1-PA8-Pad67)") (class "Default")
      (node (ref "U1") (pin "67") (pinfunction "PA8_67") (pintype "passive"))
    )
    (net (code "76") (name "unconnected-(U1-PA9{slash}OTG_FS_VBUS-Pad68)") (class "Default")
      (node (ref "U1") (pin "68") (pinfunction "PA9/OTG_FS_VBUS_68") (pintype "passive"))
    )
    (net (code "77") (name "unconnected-(U1-PA10{slash}OTG_FS_ID-Pad69)") (class "Default")
      (node (ref "U1") (pin "69") (pinfunction "PA10/OTG_FS_ID_69") (pintype "passive"))
    )
    (net (code "78") (name "unconnected-(U1-PA11{slash}OTG_FS_DM-Pad70)") (class "Default")
      (node (ref "U1") (pin "70") (pinfunction "PA11/OTG_FS_DM_70") (pintype "passive"))
    )
    (net (code "79") (name "unconnected-(U1-PA12{slash}OTG_FS_DP-Pad71)") (class "Default")
      (node (ref "U1") (pin "71") (pinfunction "PA12/OTG_FS_DP_71") (pintype "passive"))
    )
    (net (code "80") (name "unconnected-(U1-PB0-Pad35)") (class "Default")
      (node (ref "U1") (pin "35") (pinfunction "PB0_35") (pintype "passive"))
    )
    (net (code "81") (name "unconnected-(U1-PB1-Pad36)") (class "Default")
      (node (ref "U1") (pin "36") (pinfunction "PB1_36") (pintype "passive"))
    )
    (net (code "82") (name "unconnected-(U1-PB5-Pad91)") (class "Default")
      (node (ref "U1") (pin "91") (pinfunction "PB5_91") (pintype "passive"))
    )
    (net (code "83") (name "unconnected-(U1-PB14{slash}SPI2_MISO-Pad53)") (class "Default")
      (node (ref "U1") (pin "53") (pinfunction "PB14/SPI2_MISO_53") (pintype "passive"))
    )
    (net (code "84") (name "unconnected-(U1-PC0-Pad15)") (class "Default")
      (node (ref "U1") (pin "15") (pinfunction "PC0_15") (pintype "passive"))
    )
    (net (code "85") (name "unconnected-(U1-PC1-Pad16)") (class "Default")
      (node (ref "U1") (pin "16") (pinfunction "PC1_16") (pintype "passive"))
    )
    (net (code "86") (name "unconnected-(U1-PC2-Pad17)") (class "Default")
      (node (ref "U1") (pin "17") (pinfunction "PC2_17") (pintype "passive"))
    )
    (net (code "87") (name "unconnected-(U1-PC3-Pad18)") (class "Default")
      (node (ref "U1") (pin "18") (pinfunction "PC3_18") (pintype "passive"))
    )
    (net (code "88") (name "unconnected-(U1-PC4-Pad33)") (class "Default")
      (node (ref "U1") (pin "33") (pinfunction "PC4_33") (pintype "passive"))
    )
    (net (code "89") (name "unconnected-(U1-PC5-Pad34)") (class "Default")
      (node (ref "U1") (pin "34") (pinfunction "PC5_34") (pintype "passive"))
    )
    (net (code "90") (name "unconnected-(U1-PD0-Pad81)") (class "Default")
      (node (ref "U1") (pin "81") (pinfunction "PD0_81") (pintype "passive"))
    )
    (net (code "91") (name "unconnected-(U1-PD1-Pad82)") (class "Default")
      (node (ref "U1") (pin "82") (pinfunction "PD1_82") (pintype "passive"))
    )
    (net (code "92") (name "unconnected-(U1-PD3{slash}USART2_CTS-Pad84)") (class "Default")
      (node (ref "U1") (pin "84") (pinfunction "PD3/USART2_CTS_84") (pintype "input"))
    )
    (net (code "93") (name "unconnected-(U1-PD7-Pad88)") (class "Default")
      (node (ref "U1") (pin "88") (pinfunction "PD7_88") (pintype "passive"))
    )
    (net (code "94") (name "unconnected-(U1-PD8-Pad55)") (class "Default")
      (node (ref "U1") (pin "55") (pinfunction "PD8_55") (pintype "passive"))
    )
    (net (code "95") (name "unconnected-(U1-PE0-Pad97)") (class "Default")
      (node (ref "U1") (pin "97") (pinfunction "PE0_97") (pintype "passive"))
    )
    (net (code "96") (name "unconnected-(U1-PE1-Pad98)") (class "Default")
      (node (ref "U1") (pin "98") (pinfunction "PE1_98") (pintype "passive"))
    )
    (net (code "97") (name "unconnected-(U1-PE5-Pad4)") (class "Default")
      (node (ref "U1") (pin "4") (pinfunction "PE5_4") (pintype "passive"))
    )
    (net (code "98") (name "unconnected-(U1-PE6-Pad5)") (class "Default")
      (node (ref "U1") (pin "5") (pinfunction "PE6_5") (pintype "passive"))
    )
    (net (code "99") (name "unconnected-(U1-PE7-Pad38)") (class "Default")
      (node (ref "U1") (pin "38") (pinfunction "PE7_38") (pintype "passive"))
    )
    (net (code "100") (name "unconnected-(U1-PE8-Pad39)") (class "Default")
      (node (ref "U1") (pin "39") (pinfunction "PE8_39") (pintype "passive"))
    )
    (net (code "101") (name "unconnected-(U1-PE10-Pad41)") (class "Default")
      (node (ref "U1") (pin "41") (pinfunction "PE10_41") (pintype "passive"))
    )
    (net (code "102") (name "unconnected-(U1-PE11-Pad42)") (class "Default")
      (node (ref "U1") (pin "42") (pinfunction "PE11_42") (pintype "passive"))
    )
    (net (code "103") (name "unconnected-(U1-PE12-Pad43)") (class "Default")
      (node (ref "U1") (pin "43") (pinfunction "PE12_43") (pintype "passive"))
    )
    (net (code "104") (name "unconnected-(U1-PE13-Pad44)") (class "Default")
      (node (ref "U1") (pin "44") (pinfunction "PE13_44") (pintype "passive"))
    )
    (net (code "105") (name "unconnected-(U1-PE14-Pad45)") (class "Default")
      (node (ref "U1") (pin "45") (pinfunction "PE14_45") (pintype "passive"))
    )
    (net (code "106") (name "unconnected-(U1-PE15-Pad46)") (class "Default")
      (node (ref "U1") (pin "46") (pinfunction "PE15_46") (pintype "passive"))
    )
    (net (code "107") (name "unconnected-(U2-NC-Pad2)") (class "Default")
      (node (ref "U2") (pin "2") (pinfunction "NC_2") (pintype "power_in"))
    )
    (net (code "108") (name "unconnected-(U2-NC-Pad3)") (class "Default")
      (node (ref "U2") (pin "3") (pinfunction "NC_3") (pintype "power_in"))
    )
  )
)
